# daughter-double2.net
KiCad netlist of a schematic drawn in EAGLE
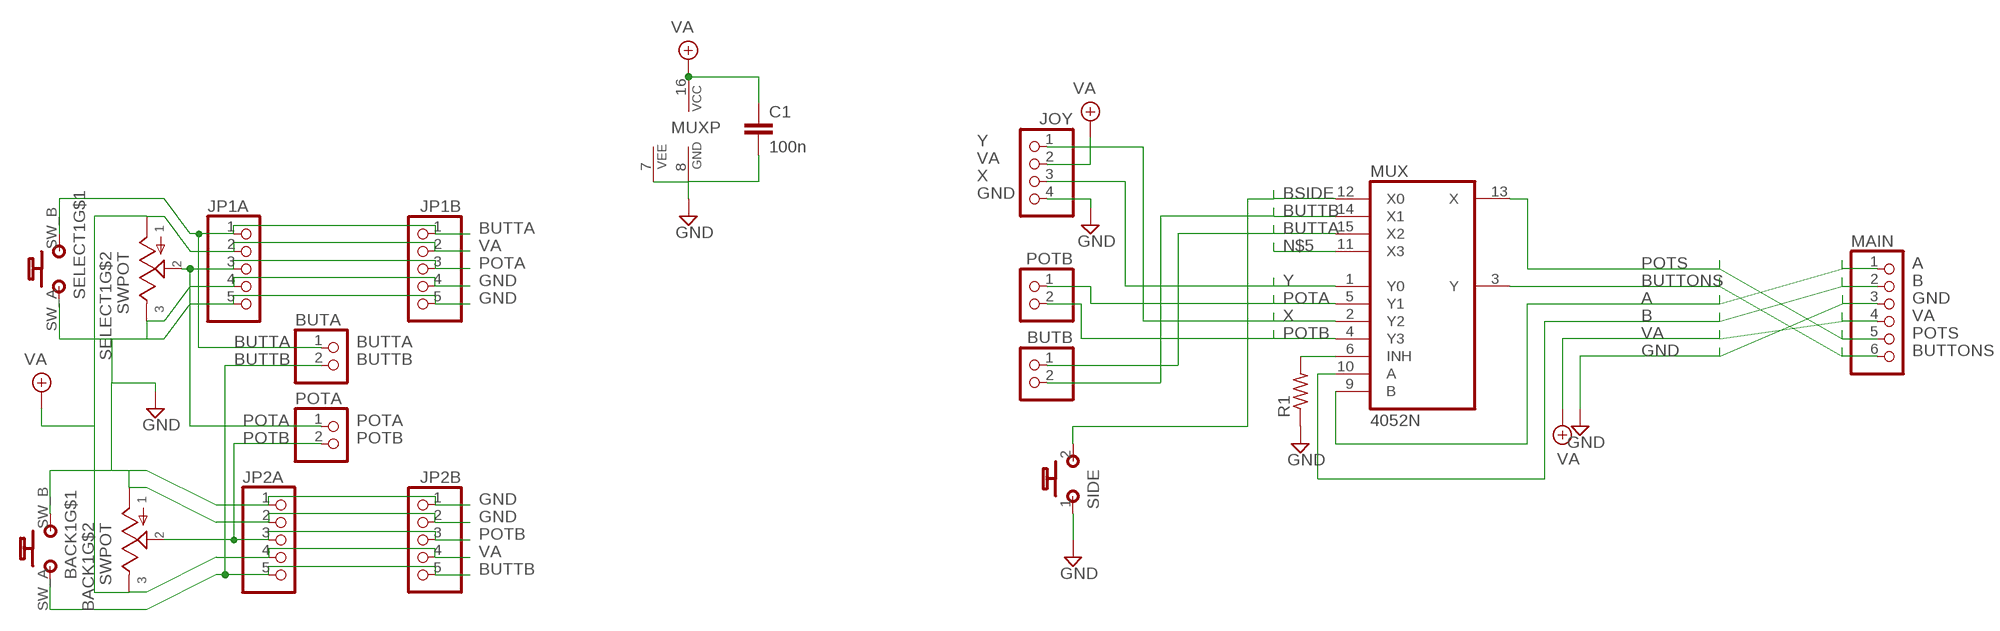
[diagram p0: schematic, sheet 1]

(export (version "E")
  (design (tool "Eeschema 10.0.6"))
  (components
    (comp (ref "BACK1")
      (value "SWPOT")
      (footprint "eagle-import:SWPOT")
      (libsource (lib "eagle-import") (part "SWPOT"))
    )
    (comp (ref "BUTA")
      (value "PINHD-1X2")
      (footprint "eagle-import:1X02")
      (libsource (lib "eagle-import") (part "PINHD-1X2"))
    )
    (comp (ref "BUTB")
      (value "PINHD-1X2")
      (footprint "eagle-import:1X02")
      (libsource (lib "eagle-import") (part "PINHD-1X2"))
    )
    (comp (ref "C1")
      (value "100n")
      (footprint "eagle-import:050X030_050_3")
      (libsource (lib "eagle-import") (part "050X030_050"))
    )
    (comp (ref "JOY")
      (value "PINHD-1X4")
      (footprint "eagle-import:1X04")
      (libsource (lib "eagle-import") (part "PINHD-1X4"))
    )
    (comp (ref "JP1A")
      (value "PINHD-1X5")
      (footprint "eagle-import:1X05")
      (libsource (lib "eagle-import") (part "PINHD-1X5"))
    )
    (comp (ref "JP1B")
      (value "PINHD-1X5")
      (footprint "eagle-import:1X05")
      (libsource (lib "eagle-import") (part "PINHD-1X5"))
    )
    (comp (ref "JP2A")
      (value "PINHD-1X5")
      (footprint "eagle-import:1X05")
      (libsource (lib "eagle-import") (part "PINHD-1X5"))
    )
    (comp (ref "JP2B")
      (value "PINHD-1X5")
      (footprint "eagle-import:1X05")
      (libsource (lib "eagle-import") (part "PINHD-1X5"))
    )
    (comp (ref "MAIN")
      (value "PINHD-1X6")
      (footprint "eagle-import:1X06")
      (libsource (lib "eagle-import") (part "PINHD-1X6"))
    )
    (comp (ref "MUX")
      (value "4052N")
      (footprint "eagle-import:DIL16")
      (libsource (lib "eagle-import") (part "4052N"))
    )
    (comp (ref "POTA")
      (value "PINHD-1X2")
      (footprint "eagle-import:1X02")
      (libsource (lib "eagle-import") (part "PINHD-1X2"))
    )
    (comp (ref "POTB")
      (value "PINHD-1X2")
      (footprint "eagle-import:1X02")
      (libsource (lib "eagle-import") (part "PINHD-1X2"))
    )
    (comp (ref "R1")
      (value "6MM.1")
      (footprint "eagle-import:R0207_1V")
      (libsource (lib "eagle-import") (part "6MM.1"))
    )
    (comp (ref "SELECT1")
      (value "SWPOT")
      (footprint "eagle-import:SWPOT")
      (libsource (lib "eagle-import") (part "SWPOT"))
    )
    (comp (ref "SIDE")
      (value "MOMENTARYSPST1")
      (footprint "eagle-import:SPST")
      (libsource (lib "eagle-import") (part "MOMENTARYSPST1"))
    )
  )
  (nets
    (net (code "1") (name "/A") (class "Default")
      (node (ref "MAIN") (pin "1") (pinfunction "1_1") (pintype "passive"))
      (node (ref "MUX") (pin "9") (pinfunction "B_9") (pintype "input"))
    )
    (net (code "2") (name "/B") (class "Default")
      (node (ref "MAIN") (pin "2") (pinfunction "2_2") (pintype "passive"))
      (node (ref "MUX") (pin "10") (pinfunction "A_10") (pintype "input"))
    )
    (net (code "3") (name "/BSIDE") (class "Default")
      (node (ref "MUX") (pin "12") (pinfunction "X0_12") (pintype "bidirectional"))
      (node (ref "SIDE") (pin "2") (pinfunction "S_2") (pintype "passive"))
    )
    (net (code "4") (name "/BUTTA") (class "Default")
      (node (ref "BUTA") (pin "1") (pinfunction "1_1") (pintype "passive"))
      (node (ref "BUTB") (pin "1") (pinfunction "1_1") (pintype "passive"))
      (node (ref "JP1A") (pin "1") (pinfunction "1_1") (pintype "passive"))
      (node (ref "JP1B") (pin "1") (pinfunction "1_1") (pintype "passive"))
      (node (ref "MUX") (pin "15") (pinfunction "X2_15") (pintype "bidirectional"))
      (node (ref "SELECT1") (pin "SW_B") (pinfunction "B_B_SW_B") (pintype "passive"))
    )
    (net (code "5") (name "/BUTTB") (class "Default")
      (node (ref "BACK1") (pin "SW_A") (pinfunction "B_A_SW_A") (pintype "passive"))
      (node (ref "BUTA") (pin "2") (pinfunction "2_2") (pintype "passive"))
      (node (ref "BUTB") (pin "2") (pinfunction "2_2") (pintype "passive"))
      (node (ref "JP2A") (pin "5") (pinfunction "5_5") (pintype "passive"))
      (node (ref "JP2B") (pin "5") (pinfunction "5_5") (pintype "passive"))
      (node (ref "MUX") (pin "14") (pinfunction "X1_14") (pintype "bidirectional"))
    )
    (net (code "6") (name "/BUTTONS") (class "Default")
      (node (ref "MAIN") (pin "6") (pinfunction "6_6") (pintype "passive"))
      (node (ref "MUX") (pin "3") (pinfunction "Y_3") (pintype "bidirectional"))
    )
    (net (code "7") (name "/N$5") (class "Default")
      (node (ref "MUX") (pin "11") (pinfunction "X3_11") (pintype "bidirectional"))
    )
    (net (code "8") (name "/POTA") (class "Default")
      (node (ref "JP1A") (pin "3") (pinfunction "3_3") (pintype "passive"))
      (node (ref "JP1B") (pin "3") (pinfunction "3_3") (pintype "passive"))
      (node (ref "MUX") (pin "5") (pinfunction "Y1_5") (pintype "bidirectional"))
      (node (ref "POTA") (pin "1") (pinfunction "1_1") (pintype "passive"))
      (node (ref "POTB") (pin "1") (pinfunction "1_1") (pintype "passive"))
      (node (ref "SELECT1") (pin "POT_W") (pinfunction "POT_W_POT_W") (pintype "passive"))
    )
    (net (code "9") (name "/POTB") (class "Default")
      (node (ref "BACK1") (pin "POT_W") (pinfunction "POT_W_POT_W") (pintype "passive"))
      (node (ref "JP2A") (pin "3") (pinfunction "3_3") (pintype "passive"))
      (node (ref "JP2B") (pin "3") (pinfunction "3_3") (pintype "passive"))
      (node (ref "MUX") (pin "4") (pinfunction "Y3_4") (pintype "bidirectional"))
      (node (ref "POTA") (pin "2") (pinfunction "2_2") (pintype "passive"))
      (node (ref "POTB") (pin "2") (pinfunction "2_2") (pintype "passive"))
    )
    (net (code "10") (name "/POTS") (class "Default")
      (node (ref "MAIN") (pin "5") (pinfunction "5_5") (pintype "passive"))
      (node (ref "MUX") (pin "13") (pinfunction "X_13") (pintype "bidirectional"))
    )
    (net (code "11") (name "/X") (class "Default")
      (node (ref "JOY") (pin "1") (pinfunction "1_1") (pintype "passive"))
      (node (ref "MUX") (pin "2") (pinfunction "Y2_2") (pintype "bidirectional"))
    )
    (net (code "12") (name "/Y") (class "Default")
      (node (ref "JOY") (pin "3") (pinfunction "3_3") (pintype "passive"))
      (node (ref "MUX") (pin "1") (pinfunction "Y0_1") (pintype "bidirectional"))
    )
    (net (code "13") (name "GND") (class "Default")
      (node (ref "BACK1") (pin "POT_B") (pinfunction "POT_B_POT_B") (pintype "passive"))
      (node (ref "BACK1") (pin "SW_B") (pinfunction "B_B_SW_B") (pintype "passive"))
      (node (ref "C1") (pin "2") (pinfunction "2_2") (pintype "passive"))
      (node (ref "JOY") (pin "4") (pinfunction "4_4") (pintype "passive"))
      (node (ref "JP1A") (pin "4") (pinfunction "4_4") (pintype "passive"))
      (node (ref "JP1A") (pin "5") (pinfunction "5_5") (pintype "passive"))
      (node (ref "JP1B") (pin "4") (pinfunction "4_4") (pintype "passive"))
      (node (ref "JP1B") (pin "5") (pinfunction "5_5") (pintype "passive"))
      (node (ref "JP2A") (pin "1") (pinfunction "1_1") (pintype "passive"))
      (node (ref "JP2A") (pin "2") (pinfunction "2_2") (pintype "passive"))
      (node (ref "JP2B") (pin "1") (pinfunction "1_1") (pintype "passive"))
      (node (ref "JP2B") (pin "2") (pinfunction "2_2") (pintype "passive"))
      (node (ref "MAIN") (pin "3") (pinfunction "3_3") (pintype "passive"))
      (node (ref "MUX") (pin "7") (pinfunction "VEE_7") (pintype "power_in"))
      (node (ref "MUX") (pin "8") (pinfunction "GND_8") (pintype "power_in"))
      (node (ref "R1") (pin "1") (pinfunction "1_1") (pintype "passive"))
      (node (ref "SELECT1") (pin "POT_A") (pinfunction "POT_A_POT_A") (pintype "passive"))
      (node (ref "SELECT1") (pin "SW_A") (pinfunction "B_A_SW_A") (pintype "passive"))
      (node (ref "SIDE") (pin "1") (pinfunction "P_1") (pintype "passive"))
    )
    (net (code "14") (name "Net-(MUXA-INH)") (class "Default")
      (node (ref "MUX") (pin "6") (pinfunction "INH_6") (pintype "input"))
      (node (ref "R1") (pin "2") (pinfunction "2_2") (pintype "passive"))
    )
    (net (code "15") (name "VA") (class "Default")
      (node (ref "BACK1") (pin "POT_A") (pinfunction "POT_A_POT_A") (pintype "passive"))
      (node (ref "C1") (pin "1") (pinfunction "1_1") (pintype "passive"))
      (node (ref "JOY") (pin "2") (pinfunction "2_2") (pintype "passive"))
      (node (ref "JP1A") (pin "2") (pinfunction "2_2") (pintype "passive"))
      (node (ref "JP1B") (pin "2") (pinfunction "2_2") (pintype "passive"))
      (node (ref "JP2A") (pin "4") (pinfunction "4_4") (pintype "passive"))
      (node (ref "JP2B") (pin "4") (pinfunction "4_4") (pintype "passive"))
      (node (ref "MAIN") (pin "4") (pinfunction "4_4") (pintype "passive"))
      (node (ref "MUX") (pin "16") (pinfunction "VCC_16") (pintype "power_in"))
      (node (ref "SELECT1") (pin "POT_B") (pinfunction "POT_B_POT_B") (pintype "passive"))
    )
  )
)
